# Circadian2.net
KiCad netlist of a schematic drawn in Altium Designer
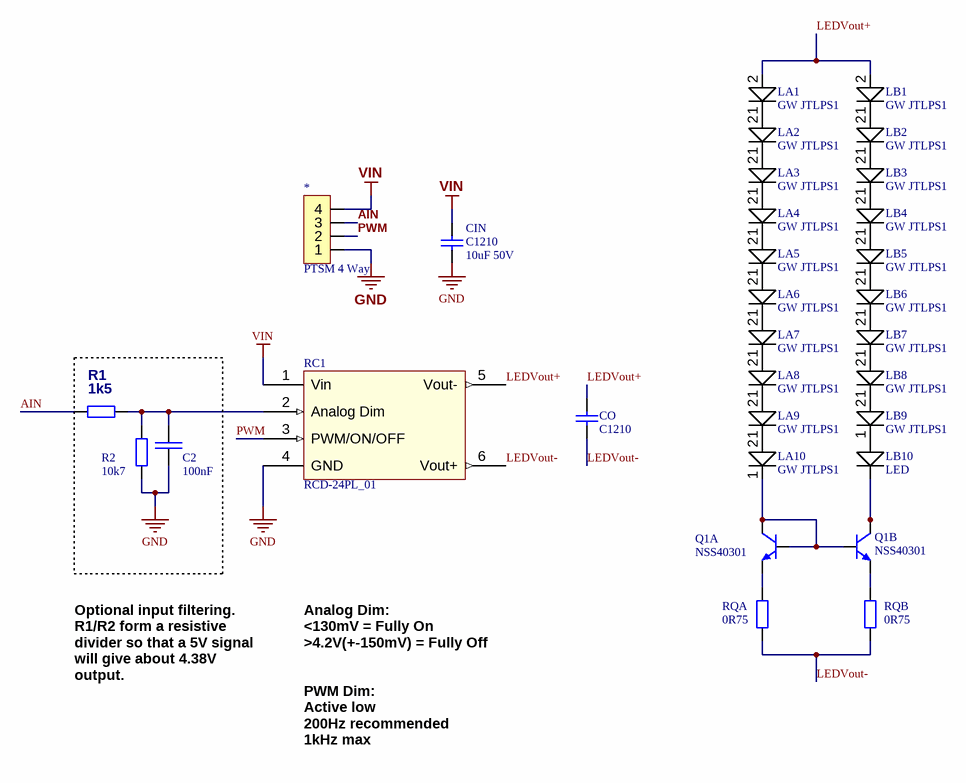
[diagram p0: Circadian2.SchDoc]

(export (version "E")
  (design (tool "Eeschema 10.0.6"))
  (components
    (comp (ref "*")
      (value "PTSM 4 Way")
      (footprint "PTSM - 4 Way Vertical")
      (libsource (lib "wes") (part "PTSM 4 Way"))
    )
    (comp (ref "C2")
      (value "100nF")
      (footprint "CAP_SM0603_YAGEOCC2_N")
      (description "CAP 100nF SM0603 X7R 50V YAGEO CC2")
      (fields
        (field (name "MANUFACTURER") "Yageo")
        (field (name "MANUFACTURER PART NUMBER") "CC0603KRX7R9BB104")
      )
      (libsource (lib "Integrated_Library_Yageo") (part "CC0603KRX7R9BB104"))
    )
    (comp (ref "CIN")
      (value "C1210")
      (footprint "1210")
      (description "Ceramic Chip Capacitor - Standard")
      (fields (field (name "ALTIUM_VALUE") "10uF 50V") (field (name "PUBLISHER") "Altium Limited"))
      (libsource (lib "KEMET Chip Capacitor") (part "C1210"))
    )
    (comp (ref "CO")
      (value "C1210")
      (footprint "1210")
      (description "Ceramic Chip Capacitor - Standard")
      (fields (field (name "PUBLISHER") "Altium Limited"))
      (libsource (lib "KEMET Chip Capacitor") (part "C1210"))
    )
    (comp (ref "LA1")
      (value "GW JTLPS1")
      (footprint "E2835")
      (description "Osram LED")
      (libsource (lib "wes") (part "GW JTLPS1.CM LED"))
    )
    (comp (ref "LA2")
      (value "GW JTLPS1")
      (footprint "E2835")
      (description "Osram LED")
      (libsource (lib "wes") (part "GW JTLPS1.CM LED"))
    )
    (comp (ref "LA3")
      (value "GW JTLPS1")
      (footprint "E2835")
      (description "Osram LED")
      (libsource (lib "wes") (part "GW JTLPS1.CM LED"))
    )
    (comp (ref "LA4")
      (value "GW JTLPS1")
      (footprint "E2835")
      (description "Osram LED")
      (libsource (lib "wes") (part "GW JTLPS1.CM LED"))
    )
    (comp (ref "LA5")
      (value "GW JTLPS1")
      (footprint "E2835")
      (description "Osram LED")
      (libsource (lib "wes") (part "GW JTLPS1.CM LED"))
    )
    (comp (ref "LA6")
      (value "GW JTLPS1")
      (footprint "E2835")
      (description "Osram LED")
      (libsource (lib "wes") (part "GW JTLPS1.CM LED"))
    )
    (comp (ref "LA7")
      (value "GW JTLPS1")
      (footprint "E2835")
      (description "Osram LED")
      (libsource (lib "wes") (part "GW JTLPS1.CM LED"))
    )
    (comp (ref "LA8")
      (value "GW JTLPS1")
      (footprint "E2835")
      (description "Osram LED")
      (libsource (lib "wes") (part "GW JTLPS1.CM LED"))
    )
    (comp (ref "LA9")
      (value "GW JTLPS1")
      (footprint "E2835")
      (description "Osram LED")
      (libsource (lib "wes") (part "GW JTLPS1.CM LED"))
    )
    (comp (ref "LA10")
      (value "GW JTLPS1")
      (footprint "E2835")
      (description "Osram LED")
      (libsource (lib "wes") (part "GW JTLPS1.CM LED"))
    )
    (comp (ref "LB1")
      (value "GW JTLPS1")
      (footprint "E2835")
      (description "Osram LED")
      (libsource (lib "wes") (part "GW JTLPS1.CM LED"))
    )
    (comp (ref "LB2")
      (value "GW JTLPS1")
      (footprint "E2835")
      (description "Osram LED")
      (libsource (lib "wes") (part "GW JTLPS1.CM LED"))
    )
    (comp (ref "LB3")
      (value "GW JTLPS1")
      (footprint "E2835")
      (description "Osram LED")
      (libsource (lib "wes") (part "GW JTLPS1.CM LED"))
    )
    (comp (ref "LB4")
      (value "GW JTLPS1")
      (footprint "E2835")
      (description "Osram LED")
      (libsource (lib "wes") (part "GW JTLPS1.CM LED"))
    )
    (comp (ref "LB5")
      (value "GW JTLPS1")
      (footprint "E2835")
      (description "Osram LED")
      (libsource (lib "wes") (part "GW JTLPS1.CM LED"))
    )
    (comp (ref "LB6")
      (value "GW JTLPS1")
      (footprint "E2835")
      (description "Osram LED")
      (libsource (lib "wes") (part "GW JTLPS1.CM LED"))
    )
    (comp (ref "LB7")
      (value "GW JTLPS1")
      (footprint "E2835")
      (description "Osram LED")
      (libsource (lib "wes") (part "GW JTLPS1.CM LED"))
    )
    (comp (ref "LB8")
      (value "GW JTLPS1")
      (footprint "E2835")
      (description "Osram LED")
      (libsource (lib "wes") (part "GW JTLPS1.CM LED"))
    )
    (comp (ref "LB9")
      (value "GW JTLPS1")
      (footprint "E2835")
      (description "Osram LED")
      (libsource (lib "wes") (part "GW JTLPS1.CM LED"))
    )
    (comp (ref "LB10")
      (value "LED")
      (footprint "E2835")
      (description "Osram LED")
      (libsource (lib "wes") (part "LED"))
    )
    (comp (ref "Q1") (value "NSS40301") (footprint "SOIC8") (libsource (lib "wes") (part "NSS40301")))
    (comp (ref "R1")
      (value "1k5")
      (footprint "RES_SM0603_YAGEORC_N")
      (description "RES 10R SM0603 YAGEO RC_L")
      (fields
        (field (name "MANUFACTURER") "Yageo")
        (field (name "MANUFACTURER PART NUMBER") "RC0603FR-0710RL")
      )
      (libsource (lib "Integrated_Library_Yageo") (part "RC0603FR-0710RL"))
    )
    (comp (ref "R2")
      (value "10k7")
      (footprint "RES_SM0603_YAGEORC_N")
      (description "RES 10R SM0603 YAGEO RC_L")
      (fields
        (field (name "MANUFACTURER") "Yageo")
        (field (name "MANUFACTURER PART NUMBER") "RC0603FR-0710RL")
      )
      (libsource (lib "") (part "RC0603FR-0710RL_1"))
    )
    (comp (ref "RC1")
      (value "RCD-24PL_01")
      (footprint "RCD-24PL_01")
      (libsource (lib "wes") (part "RCD-24PL_01"))
    )
    (comp (ref "RQA")
      (value "0R75")
      (footprint "RES_SM0603_YAGEORC_N")
      (description "RES 10R SM0603 YAGEO RC_L")
      (fields
        (field (name "MANUFACTURER") "Yageo")
        (field (name "MANUFACTURER PART NUMBER") "RC0603FR-0710RL")
      )
      (libsource (lib "") (part "RC0603FR-0710RL_1"))
    )
    (comp (ref "RQB")
      (value "0R75")
      (footprint "RES_SM0603_YAGEORC_N")
      (description "RES 10R SM0603 YAGEO RC_L")
      (fields
        (field (name "MANUFACTURER") "Yageo")
        (field (name "MANUFACTURER PART NUMBER") "RC0603FR-0710RL")
      )
      (libsource (lib "") (part "RC0603FR-0710RL_1"))
    )
  )
  (nets
    (net (code "1") (name "/AIN") (class "Default")
      (node (ref "*") (pin "3") (pinfunction "3_3") (pintype "passive"))
      (node (ref "R1") (pin "2") (pintype "passive"))
    )
    (net (code "2") (name "/LEDVout+") (class "Default")
      (node (ref "CO") (pin "1") (pinfunction "1_1") (pintype "passive"))
      (node (ref "LA1") (pin "2") (pinfunction "A_2") (pintype "power_in"))
      (node (ref "LB1") (pin "2") (pinfunction "A_2") (pintype "power_in"))
      (node (ref "RC1") (pin "5") (pinfunction "Vout-_5") (pintype "output"))
    )
    (net (code "3") (name "/LEDVout-") (class "Default")
      (node (ref "CO") (pin "2") (pinfunction "2_2") (pintype "passive"))
      (node (ref "RC1") (pin "6") (pinfunction "Vout+_6") (pintype "output"))
      (node (ref "RQA") (pin "1") (pintype "passive"))
      (node (ref "RQB") (pin "1") (pintype "passive"))
    )
    (net (code "4") (name "/PWM") (class "Default")
      (node (ref "*") (pin "2") (pinfunction "2_2") (pintype "passive"))
      (node (ref "RC1") (pin "3") (pinfunction "PWM/ON/OFF_3") (pintype "input"))
    )
    (net (code "5") (name "GND") (class "Default")
      (node (ref "*") (pin "1") (pinfunction "1_1") (pintype "passive"))
      (node (ref "C2") (pin "2") (pintype "passive"))
      (node (ref "CIN") (pin "2") (pinfunction "2_2") (pintype "passive"))
      (node (ref "R2") (pin "1") (pintype "passive"))
      (node (ref "RC1") (pin "4") (pinfunction "GND_4") (pintype "power_in"))
    )
    (net (code "6") (name "Net-(LA1-K)") (class "Default")
      (node (ref "LA1") (pin "1") (pinfunction "K_1") (pintype "power_in"))
      (node (ref "LA2") (pin "2") (pinfunction "A_2") (pintype "power_in"))
    )
    (net (code "7") (name "Net-(LA2-K)") (class "Default")
      (node (ref "LA2") (pin "1") (pinfunction "K_1") (pintype "power_in"))
      (node (ref "LA3") (pin "2") (pinfunction "A_2") (pintype "power_in"))
    )
    (net (code "8") (name "Net-(LA3-K)") (class "Default")
      (node (ref "LA3") (pin "1") (pinfunction "K_1") (pintype "power_in"))
      (node (ref "LA4") (pin "2") (pinfunction "A_2") (pintype "power_in"))
    )
    (net (code "9") (name "Net-(LA4-K)") (class "Default")
      (node (ref "LA4") (pin "1") (pinfunction "K_1") (pintype "power_in"))
      (node (ref "LA5") (pin "2") (pinfunction "A_2") (pintype "power_in"))
    )
    (net (code "10") (name "Net-(LA5-K)") (class "Default")
      (node (ref "LA5") (pin "1") (pinfunction "K_1") (pintype "power_in"))
      (node (ref "LA6") (pin "2") (pinfunction "A_2") (pintype "power_in"))
    )
    (net (code "11") (name "Net-(LA6-K)") (class "Default")
      (node (ref "LA6") (pin "1") (pinfunction "K_1") (pintype "power_in"))
      (node (ref "LA7") (pin "2") (pinfunction "A_2") (pintype "power_in"))
    )
    (net (code "12") (name "Net-(LA7-K)") (class "Default")
      (node (ref "LA7") (pin "1") (pinfunction "K_1") (pintype "power_in"))
      (node (ref "LA8") (pin "2") (pinfunction "A_2") (pintype "power_in"))
    )
    (net (code "13") (name "Net-(LA8-K)") (class "Default")
      (node (ref "LA8") (pin "1") (pinfunction "K_1") (pintype "power_in"))
      (node (ref "LA9") (pin "2") (pinfunction "A_2") (pintype "power_in"))
    )
    (net (code "14") (name "Net-(LA10-A)") (class "Default")
      (node (ref "LA10") (pin "2") (pinfunction "A_2") (pintype "power_in"))
      (node (ref "LA9") (pin "1") (pinfunction "K_1") (pintype "power_in"))
    )
    (net (code "15") (name "Net-(LA10-K)") (class "Default")
      (node (ref "LA10") (pin "1") (pinfunction "K_1") (pintype "power_in"))
      (node (ref "Q1") (pin "2") (pinfunction "B1_2") (pintype "passive"))
      (node (ref "Q1") (pin "4") (pinfunction "B2_4") (pintype "passive"))
      (node (ref "Q1") (pin "7") (pinfunction "C1_7") (pintype "passive"))
      (node (ref "Q1") (pin "8") (pinfunction "C1_8") (pintype "passive"))
    )
    (net (code "16") (name "Net-(LB1-K)") (class "Default")
      (node (ref "LB1") (pin "1") (pinfunction "K_1") (pintype "power_in"))
      (node (ref "LB2") (pin "2") (pinfunction "A_2") (pintype "power_in"))
    )
    (net (code "17") (name "Net-(LB2-K)") (class "Default")
      (node (ref "LB2") (pin "1") (pinfunction "K_1") (pintype "power_in"))
      (node (ref "LB3") (pin "2") (pinfunction "A_2") (pintype "power_in"))
    )
    (net (code "18") (name "Net-(LB3-K)") (class "Default")
      (node (ref "LB3") (pin "1") (pinfunction "K_1") (pintype "power_in"))
      (node (ref "LB4") (pin "2") (pinfunction "A_2") (pintype "power_in"))
    )
    (net (code "19") (name "Net-(LB4-K)") (class "Default")
      (node (ref "LB4") (pin "1") (pinfunction "K_1") (pintype "power_in"))
      (node (ref "LB5") (pin "2") (pinfunction "A_2") (pintype "power_in"))
    )
    (net (code "20") (name "Net-(LB5-K)") (class "Default")
      (node (ref "LB5") (pin "1") (pinfunction "K_1") (pintype "power_in"))
      (node (ref "LB6") (pin "2") (pinfunction "A_2") (pintype "power_in"))
    )
    (net (code "21") (name "Net-(LB6-K)") (class "Default")
      (node (ref "LB6") (pin "1") (pinfunction "K_1") (pintype "power_in"))
      (node (ref "LB7") (pin "2") (pinfunction "A_2") (pintype "power_in"))
    )
    (net (code "22") (name "Net-(LB7-K)") (class "Default")
      (node (ref "LB7") (pin "1") (pinfunction "K_1") (pintype "power_in"))
      (node (ref "LB8") (pin "2") (pinfunction "A_2") (pintype "power_in"))
    )
    (net (code "23") (name "Net-(LB8-K)") (class "Default")
      (node (ref "LB8") (pin "1") (pinfunction "K_1") (pintype "power_in"))
      (node (ref "LB9") (pin "2") (pinfunction "A_2") (pintype "power_in"))
    )
    (net (code "24") (name "Net-(LB10-A)") (class "Default")
      (node (ref "LB10") (pin "2") (pinfunction "A_2") (pintype "power_in"))
      (node (ref "LB9") (pin "1") (pinfunction "K_1") (pintype "power_in"))
    )
    (net (code "25") (name "Net-(LB10-K)") (class "Default")
      (node (ref "LB10") (pin "1") (pinfunction "K_1") (pintype "power_in"))
      (node (ref "Q1") (pin "5") (pinfunction "C2_5") (pintype "passive"))
      (node (ref "Q1") (pin "6") (pinfunction "C2_6") (pintype "passive"))
    )
    (net (code "26") (name "Net-(Q1A-E1)") (class "Default")
      (node (ref "Q1") (pin "1") (pinfunction "E1_1") (pintype "passive"))
      (node (ref "RQA") (pin "2") (pintype "passive"))
    )
    (net (code "27") (name "Net-(Q1B-E2)") (class "Default")
      (node (ref "Q1") (pin "3") (pinfunction "E2_3") (pintype "passive"))
      (node (ref "RQB") (pin "2") (pintype "passive"))
    )
    (net (code "28") (name "Net-(RC1-Analog_Dim)") (class "Default")
      (node (ref "C2") (pin "1") (pintype "passive"))
      (node (ref "R1") (pin "1") (pintype "passive"))
      (node (ref "R2") (pin "2") (pintype "passive"))
      (node (ref "RC1") (pin "2") (pinfunction "Analog_Dim_2") (pintype "input"))
    )
    (net (code "29") (name "VIN") (class "Default")
      (node (ref "*") (pin "4") (pinfunction "4_4") (pintype "passive"))
      (node (ref "CIN") (pin "1") (pinfunction "1_1") (pintype "passive"))
      (node (ref "RC1") (pin "1") (pinfunction "Vin_1") (pintype "power_in"))
    )
  )
)
